# 06_SOM_USB_CARD.net
KiCad netlist of a schematic drawn in Altium Designer
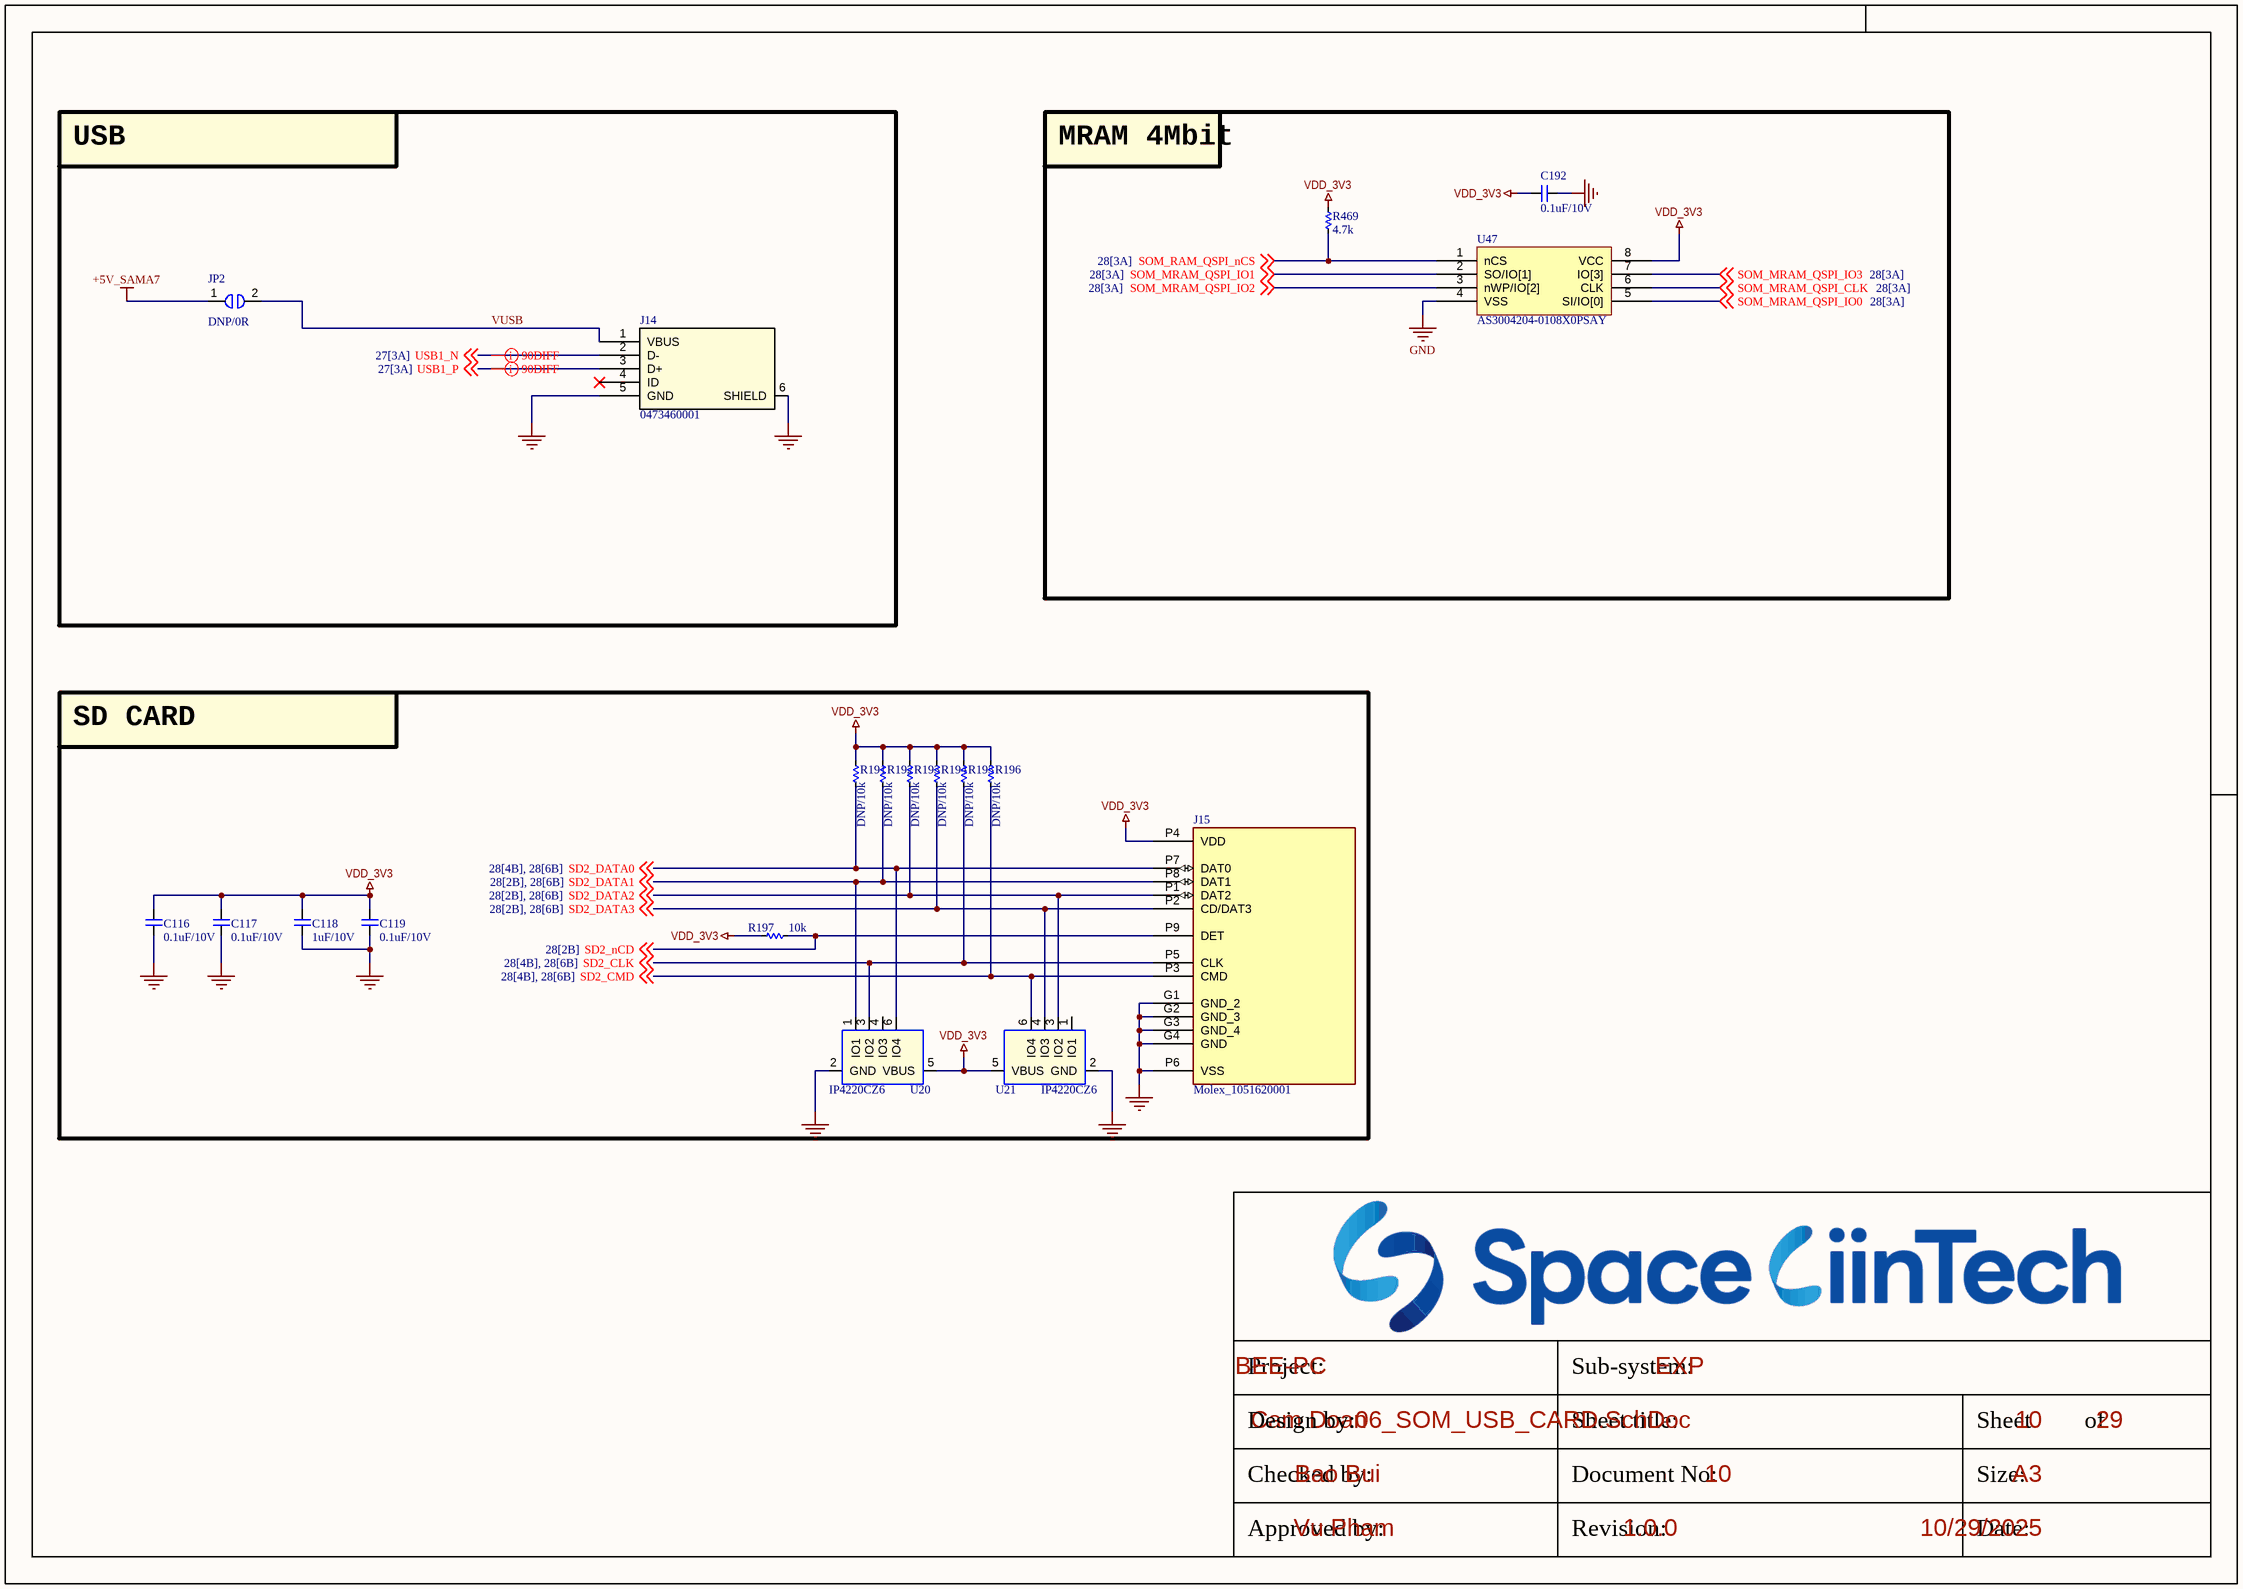
[diagram p0: 06_SOM_USB_CARD.SchDoc]

(export (version "E")
  (design (tool "Eeschema 10.0.6"))
  (components
    (comp (ref "C116")
      (value "0.1uF/10V")
      (footprint "CAP_C_1005X60")
      (description "CAP CHIP")
      (libsource (lib "LABLIB") (part "_CAP_C_2"))
    )
    (comp (ref "C117")
      (value "0.1uF/10V")
      (footprint "CAP_C_1005X60")
      (description "CAP CHIP")
      (libsource (lib "LABLIB") (part "_CAP_C_2"))
    )
    (comp (ref "C118")
      (value "1uF/10V")
      (footprint "CAP_C_1005X60")
      (description "CAP CHIP")
      (libsource (lib "LABLIB") (part "_CAP_C_2"))
    )
    (comp (ref "C119")
      (value "0.1uF/10V")
      (footprint "CAP_C_1005X60")
      (description "CAP CHIP")
      (libsource (lib "LABLIB") (part "_CAP_C_2"))
    )
    (comp (ref "C192")
      (value "0.1uF/10V")
      (footprint "CAP_C_1005X60")
      (description "CAP CHIP")
      (libsource (lib "LABLIB") (part "_CAP_C_2"))
    )
    (comp (ref "J14")
      (value "0473460001")
      (footprint "47346-0001_MOL")
      (description "No Description Available")
      (libsource (lib "obc_ver2") (part "USB_micro"))
    )
    (comp (ref "J15")
      (value "Molex_1051620001")
      (footprint "Molex_1051620001")
      (description "9 (8 + 1) Position Card Connector Secure Digital - microSDâ„¢ Surface Mount, Right Angle Gold")
      (fields (field (name "MF") "Molex") (field (name "MP") "1051620001"))
      (libsource (lib "new_component") (part "Molex_1051620001"))
    )
    (comp (ref "JP2")
      (value "DNP/0R")
      (footprint "RES_C_1608X60")
      (libsource (lib "LABLIB") (part "JUMPER_1_1"))
    )
    (comp (ref "R191")
      (value "DNP/10k")
      (footprint "RES_C_1005X40")
      (description "RES")
      (libsource (lib "LABLIB") (part "_RES_B_2"))
    )
    (comp (ref "R192")
      (value "DNP/10k")
      (footprint "RES_C_1005X40")
      (description "RES")
      (libsource (lib "LABLIB") (part "_RES_B_2"))
    )
    (comp (ref "R193")
      (value "DNP/10k")
      (footprint "RES_C_1005X40")
      (description "RES")
      (libsource (lib "LABLIB") (part "_RES_B_2"))
    )
    (comp (ref "R194")
      (value "DNP/10k")
      (footprint "RES_C_1005X40")
      (description "RES")
      (libsource (lib "LABLIB") (part "_RES_B_2"))
    )
    (comp (ref "R195")
      (value "DNP/10k")
      (footprint "RES_C_1005X40")
      (description "RES")
      (libsource (lib "LABLIB") (part "_RES_B_2"))
    )
    (comp (ref "R196")
      (value "DNP/10k")
      (footprint "RES_C_1005X40")
      (description "RES")
      (libsource (lib "LABLIB") (part "_RES_B_2"))
    )
    (comp (ref "R197")
      (value "10k")
      (footprint "RES_C_1005X40")
      (description "RES")
      (libsource (lib "LABLIB") (part "_RES_B_2"))
    )
    (comp (ref "R469")
      (value "4.7k")
      (footprint "RES_C_1005X40")
      (description "RES")
      (libsource (lib "LABLIB") (part "_RES_B_2"))
    )
    (comp (ref "U20")
      (value "IP4220CZ6")
      (footprint "SOT95P280X145-6N")
      (libsource (lib "") (part "IP4220CZ6_0_1"))
    )
    (comp (ref "U21")
      (value "IP4220CZ6")
      (footprint "SOT95P280X145-6N")
      (libsource (lib "*") (part "IP4220CZ6_0"))
    )
    (comp (ref "U47")
      (value "AS3004204-0108X0PSAY")
      (footprint "SOIC127P790X216-8")
      (libsource (lib "LABLIB") (part "IC_RAM_AS3004204-0108X0PSAY"))
    )
  )
  (nets
    (net (code "1") (name "+5V_SAMA7") (class "Default")
      (node (ref "JP2") (pin "1") (pinfunction "1_1") (pintype "passive"))
    )
    (net (code "2") (name "/VUSB") (class "Default")
      (node (ref "J14") (pin "1") (pinfunction "VBUS_1") (pintype "passive"))
      (node (ref "JP2") (pin "2") (pinfunction "2_2") (pintype "passive"))
    )
    (net (code "3") (name "GND") (class "Default")
      (node (ref "C116") (pin "1") (pinfunction "1_1") (pintype "passive"))
      (node (ref "C117") (pin "1") (pinfunction "1_1") (pintype "passive"))
      (node (ref "C118") (pin "1") (pinfunction "1_1") (pintype "passive"))
      (node (ref "C119") (pin "1") (pinfunction "1_1") (pintype "passive"))
      (node (ref "C192") (pin "1") (pinfunction "1_1") (pintype "passive"))
      (node (ref "J14") (pin "5") (pinfunction "GND_5") (pintype "power_in"))
      (node (ref "J14") (pin "6") (pinfunction "SHIELD_6") (pintype "passive"))
      (node (ref "J15") (pin "G1") (pinfunction "GND_2_G1") (pintype "passive"))
      (node (ref "J15") (pin "G2") (pinfunction "GND_3_G2") (pintype "passive"))
      (node (ref "J15") (pin "G3") (pinfunction "GND_4_G3") (pintype "passive"))
      (node (ref "J15") (pin "G4") (pinfunction "GND_G4") (pintype "passive"))
      (node (ref "J15") (pin "P6") (pinfunction "VSS_P6") (pintype "passive"))
      (node (ref "U20") (pin "2") (pinfunction "GND_2") (pintype "passive"))
      (node (ref "U21") (pin "2") (pinfunction "GND_2") (pintype "passive"))
      (node (ref "U47") (pin "4") (pinfunction "VSS_4") (pintype "passive"))
    )
    (net (code "4") (name "SD2_CLK") (class "Default")
      (node (ref "J15") (pin "P5") (pinfunction "CLK_P5") (pintype "passive"))
      (node (ref "R195") (pin "1") (pinfunction "1_1") (pintype "passive"))
      (node (ref "U20") (pin "3") (pinfunction "IO2_3") (pintype "passive"))
    )
    (net (code "5") (name "SD2_CMD") (class "Default")
      (node (ref "J15") (pin "P3") (pinfunction "CMD_P3") (pintype "passive"))
      (node (ref "R196") (pin "1") (pinfunction "1_1") (pintype "passive"))
      (node (ref "U21") (pin "6") (pinfunction "IO4_6") (pintype "passive"))
    )
    (net (code "6") (name "SD2_DATA0") (class "Default")
      (node (ref "J15") (pin "P7") (pinfunction "DAT0_P7") (pintype "bidirectional"))
      (node (ref "R191") (pin "1") (pinfunction "1_1") (pintype "passive"))
      (node (ref "U20") (pin "6") (pinfunction "IO4_6") (pintype "passive"))
    )
    (net (code "7") (name "SD2_DATA1") (class "Default")
      (node (ref "J15") (pin "P8") (pinfunction "DAT1_P8") (pintype "bidirectional"))
      (node (ref "R192") (pin "1") (pinfunction "1_1") (pintype "passive"))
      (node (ref "U20") (pin "1") (pinfunction "IO1_1") (pintype "passive"))
    )
    (net (code "8") (name "SD2_DATA2") (class "Default")
      (node (ref "J15") (pin "P1") (pinfunction "DAT2_P1") (pintype "bidirectional"))
      (node (ref "R193") (pin "1") (pinfunction "1_1") (pintype "passive"))
      (node (ref "U21") (pin "3") (pinfunction "IO2_3") (pintype "passive"))
    )
    (net (code "9") (name "SD2_DATA3") (class "Default")
      (node (ref "J15") (pin "P2") (pinfunction "CD/DAT3_P2") (pintype "passive"))
      (node (ref "R194") (pin "1") (pinfunction "1_1") (pintype "passive"))
      (node (ref "U21") (pin "4") (pinfunction "IO3_4") (pintype "passive"))
    )
    (net (code "10") (name "SD2_nCD") (class "Default")
      (node (ref "J15") (pin "P9") (pinfunction "DET_P9") (pintype "passive"))
      (node (ref "R197") (pin "2") (pinfunction "2_2") (pintype "passive"))
    )
    (net (code "11") (name "SOM_MRAM_QSPI_CLK") (class "Default")
      (node (ref "U47") (pin "6") (pinfunction "CLK_6") (pintype "passive"))
    )
    (net (code "12") (name "SOM_MRAM_QSPI_IO0") (class "Default")
      (node (ref "U47") (pin "5") (pinfunction "SI/IO[0]_5") (pintype "passive"))
    )
    (net (code "13") (name "SOM_MRAM_QSPI_IO1") (class "Default")
      (node (ref "U47") (pin "2") (pinfunction "SO/IO[1]_2") (pintype "passive"))
    )
    (net (code "14") (name "SOM_MRAM_QSPI_IO2") (class "Default")
      (node (ref "U47") (pin "3") (pinfunction "nWP/IO[2]_3") (pintype "passive"))
    )
    (net (code "15") (name "SOM_MRAM_QSPI_IO3") (class "Default")
      (node (ref "U47") (pin "7") (pinfunction "IO[3]_7") (pintype "passive"))
    )
    (net (code "16") (name "SOM_RAM_QSPI_nCS") (class "Default")
      (node (ref "R469") (pin "1") (pinfunction "1_1") (pintype "passive"))
      (node (ref "U47") (pin "1") (pinfunction "nCS_1") (pintype "passive"))
    )
    (net (code "17") (name "USB1_N") (class "Default")
      (node (ref "J14") (pin "2") (pinfunction "D-_2") (pintype "passive"))
    )
    (net (code "18") (name "USB1_P") (class "Default")
      (node (ref "J14") (pin "3") (pinfunction "D+_3") (pintype "passive"))
    )
    (net (code "19") (name "VDD_3V3") (class "Default")
      (node (ref "C116") (pin "2") (pinfunction "2_2") (pintype "passive"))
      (node (ref "C117") (pin "2") (pinfunction "2_2") (pintype "passive"))
      (node (ref "C118") (pin "2") (pinfunction "2_2") (pintype "passive"))
      (node (ref "C119") (pin "2") (pinfunction "2_2") (pintype "passive"))
      (node (ref "C192") (pin "2") (pinfunction "2_2") (pintype "passive"))
      (node (ref "J15") (pin "P4") (pinfunction "VDD_P4") (pintype "power_in"))
      (node (ref "R191") (pin "2") (pinfunction "2_2") (pintype "passive"))
      (node (ref "R192") (pin "2") (pinfunction "2_2") (pintype "passive"))
      (node (ref "R193") (pin "2") (pinfunction "2_2") (pintype "passive"))
      (node (ref "R194") (pin "2") (pinfunction "2_2") (pintype "passive"))
      (node (ref "R195") (pin "2") (pinfunction "2_2") (pintype "passive"))
      (node (ref "R196") (pin "2") (pinfunction "2_2") (pintype "passive"))
      (node (ref "R197") (pin "1") (pinfunction "1_1") (pintype "passive"))
      (node (ref "R469") (pin "2") (pinfunction "2_2") (pintype "passive"))
      (node (ref "U20") (pin "5") (pinfunction "VBUS_5") (pintype "passive"))
      (node (ref "U21") (pin "5") (pinfunction "VBUS_5") (pintype "passive"))
      (node (ref "U47") (pin "8") (pinfunction "VCC_8") (pintype "passive"))
    )
    (net (code "20") (name "unconnected-(J14-ID-Pad4)") (class "Default")
      (node (ref "J14") (pin "4") (pinfunction "ID_4") (pintype "passive+no_connect"))
    )
    (net (code "21") (name "unconnected-(U20-IO3-Pad4)") (class "Default")
      (node (ref "U20") (pin "4") (pinfunction "IO3_4") (pintype "passive"))
    )
    (net (code "22") (name "unconnected-(U21-IO1-Pad1)") (class "Default")
      (node (ref "U21") (pin "1") (pinfunction "IO1_1") (pintype "passive"))
    )
  )
)
